# GL3520_4_Ports.net
KiCad netlist of a schematic drawn in Altium Designer
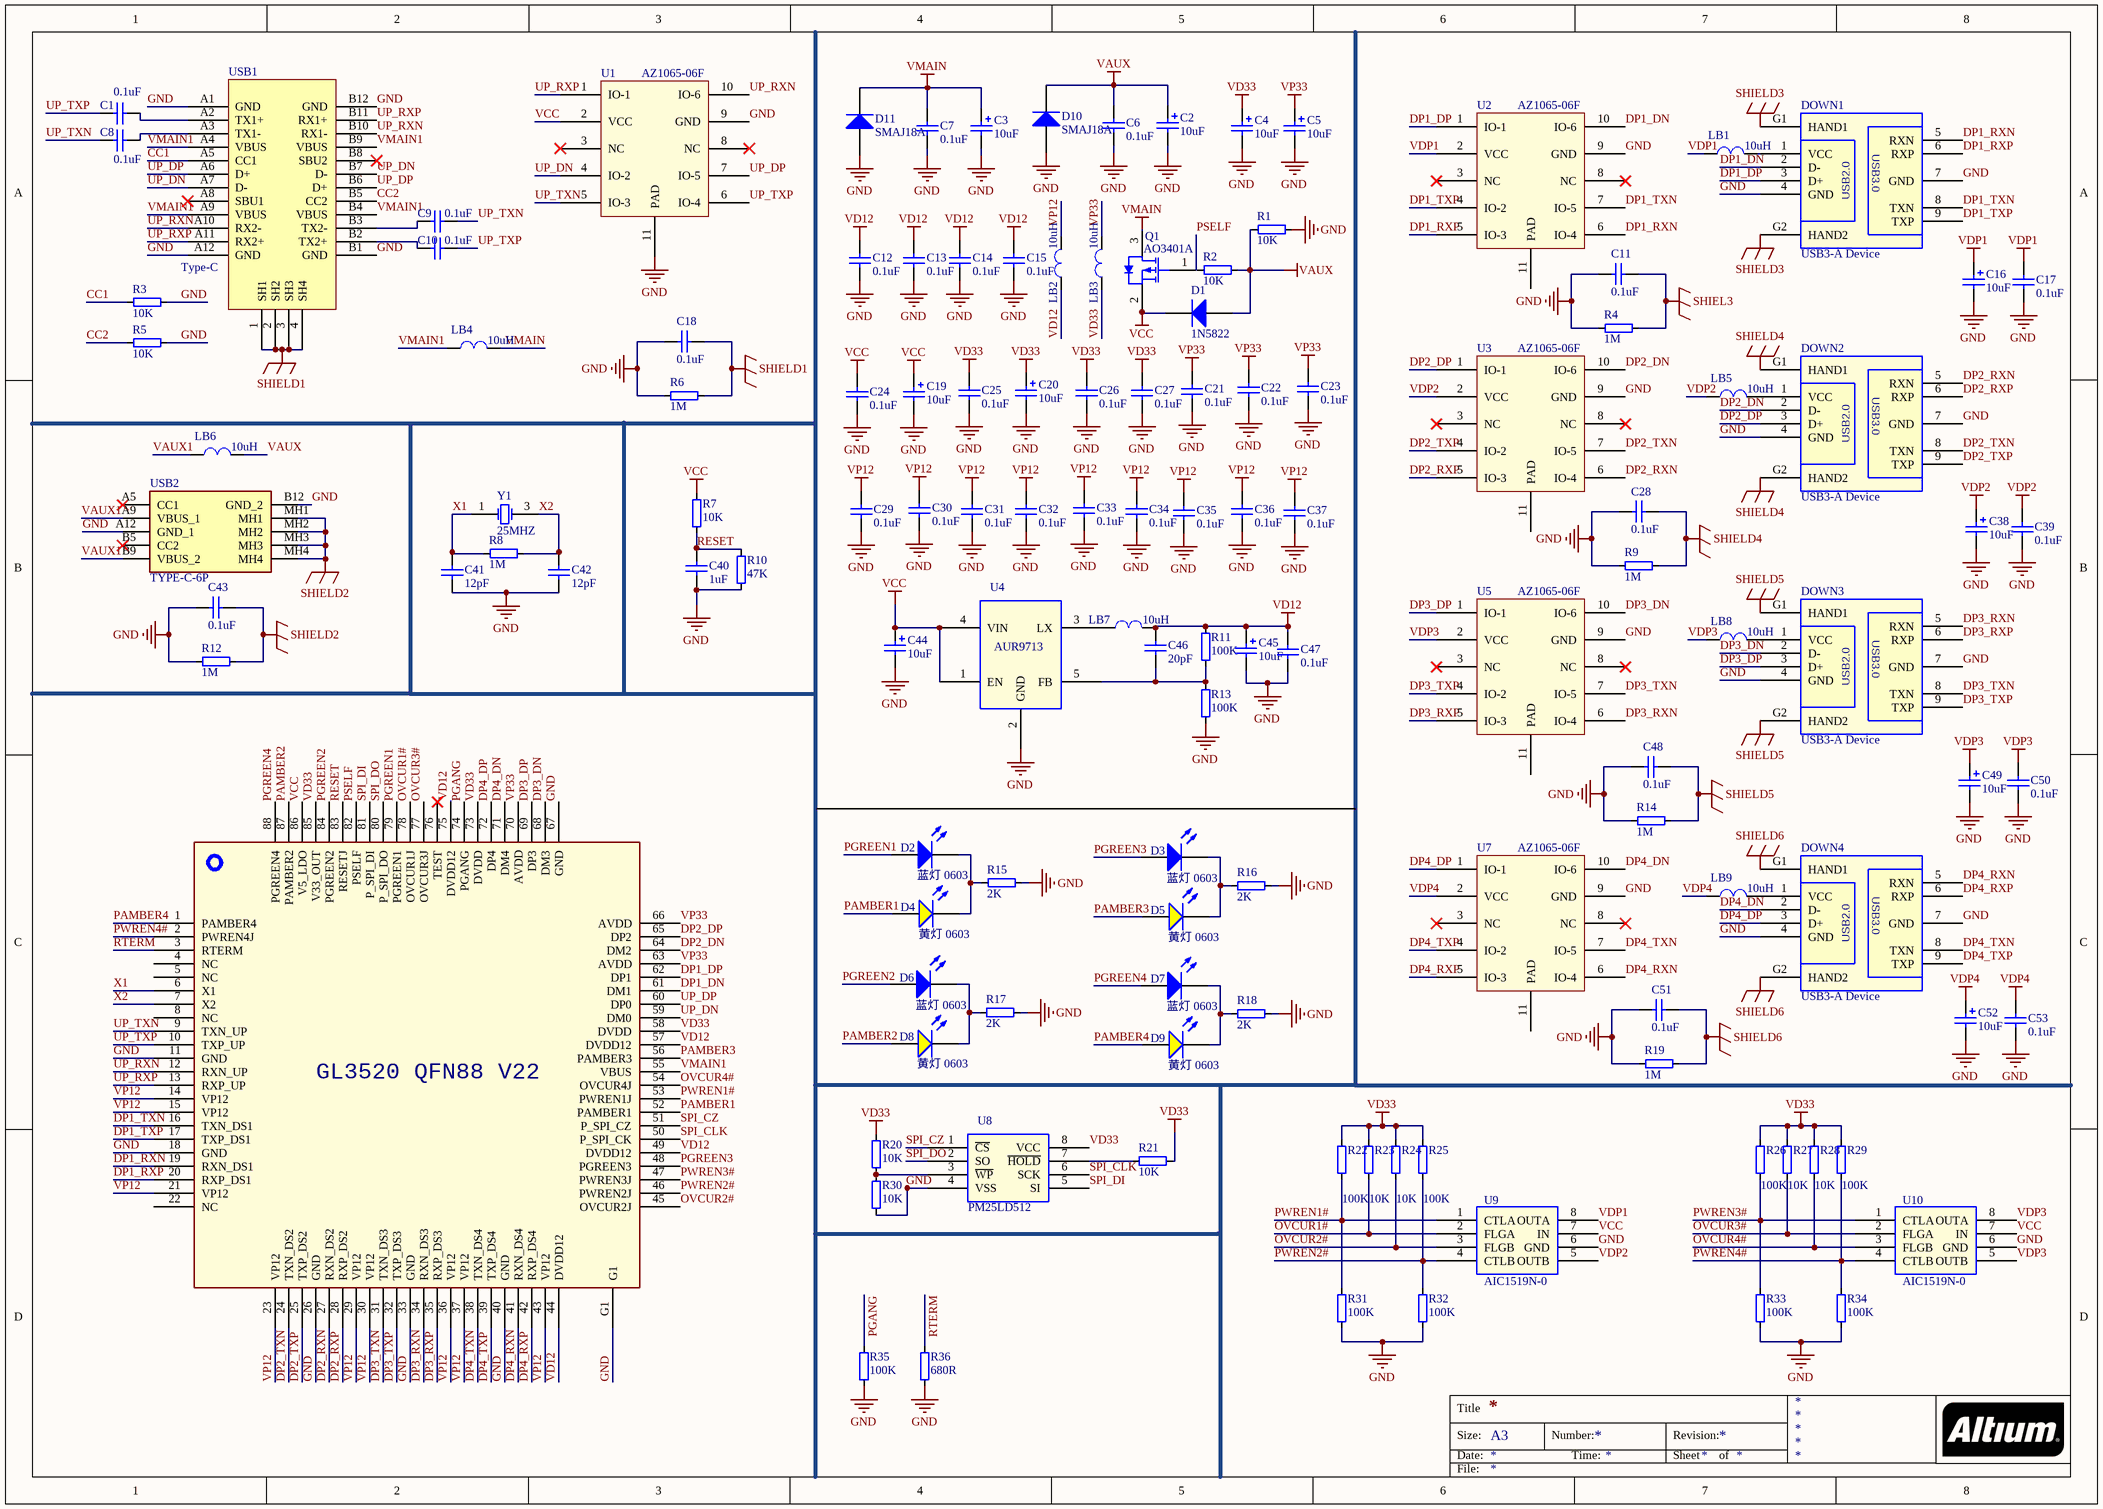
[diagram p0: GL3520 4 Ports.SchDoc]

(export (version "E")
  (design (tool "Eeschema 10.0.6"))
  (components
    (comp (ref "C1")
      (value "0.1uF")
      (footprint "C 0603_L")
      (description "贴片电容")
      (libsource (lib "嘉立创") (part "0603 2.2uF (225) 10% 16V"))
    )
    (comp (ref "C2")
      (value "10uF")
      (footprint "CASE-A_3216")
      (description "钽电容1206")
      (libsource (lib "嘉立创") (part "3216 10uF (106) 10% 16V"))
    )
    (comp (ref "C3")
      (value "10uF")
      (footprint "CASE-A_3216")
      (description "钽电容1206")
      (libsource (lib "嘉立创") (part "3216 10uF (106) 10% 16V"))
    )
    (comp (ref "C4")
      (value "10uF")
      (footprint "CASE-A_3216")
      (description "钽电容")
      (libsource (lib "嘉立创") (part "3216 10uF (106) 10% 16V"))
    )
    (comp (ref "C5")
      (value "10uF")
      (footprint "CASE-A_3216")
      (description "钽电容")
      (libsource (lib "嘉立创") (part "3216 10uF (106) 10% 16V"))
    )
    (comp (ref "C6")
      (value "0.1uF")
      (footprint "C 0603_L")
      (description "贴片电容")
      (libsource (lib "嘉立创") (part "0603 2.2uF (225) 10% 16V"))
    )
    (comp (ref "C7")
      (value "0.1uF")
      (footprint "C 0603_L")
      (description "贴片电容")
      (libsource (lib "嘉立创") (part "0603 2.2uF (225) 10% 16V"))
    )
    (comp (ref "C8")
      (value "0.1uF")
      (footprint "C 0603_L")
      (description "贴片电容")
      (libsource (lib "嘉立创") (part "0603 2.2uF (225) 10% 16V"))
    )
    (comp (ref "C9")
      (value "0.1uF")
      (footprint "C 0603_L")
      (description "贴片电容")
      (libsource (lib "嘉立创") (part "0603 2.2uF (225) 10% 16V"))
    )
    (comp (ref "C10")
      (value "0.1uF")
      (footprint "C 0603_L")
      (description "贴片电容")
      (libsource (lib "嘉立创") (part "0603 2.2uF (225) 10% 16V"))
    )
    (comp (ref "C11")
      (value "0.1uF")
      (footprint "C 0603_L")
      (description "贴片电容")
      (libsource (lib "嘉立创") (part "0603 2.2uF (225) 10% 16V"))
    )
    (comp (ref "C12")
      (value "0.1uF")
      (footprint "C 0603_L")
      (description "贴片电容")
      (libsource (lib "嘉立创") (part "0603 2.2uF (225) 10% 16V"))
    )
    (comp (ref "C13")
      (value "0.1uF")
      (footprint "C 0603_L")
      (description "贴片电容")
      (libsource (lib "嘉立创") (part "0603 2.2uF (225) 10% 16V"))
    )
    (comp (ref "C14")
      (value "0.1uF")
      (footprint "C 0603_L")
      (description "贴片电容")
      (libsource (lib "嘉立创") (part "0603 2.2uF (225) 10% 16V"))
    )
    (comp (ref "C15")
      (value "0.1uF")
      (footprint "C 0603_L")
      (description "贴片电容")
      (libsource (lib "嘉立创") (part "0603 2.2uF (225) 10% 16V"))
    )
    (comp (ref "C16")
      (value "10uF")
      (footprint "CASE-A_3216")
      (description "钽电容")
      (libsource (lib "嘉立创") (part "3216 10uF (106) 10% 16V"))
    )
    (comp (ref "C17")
      (value "0.1uF")
      (footprint "C 0603_L")
      (description "贴片电容")
      (libsource (lib "嘉立创") (part "0603 2.2uF (225) 10% 16V"))
    )
    (comp (ref "C18")
      (value "0.1uF")
      (footprint "C 0603_L")
      (description "贴片电容")
      (libsource (lib "嘉立创") (part "0603 2.2uF (225) 10% 16V"))
    )
    (comp (ref "C19")
      (value "10uF")
      (footprint "CASE-A_3216")
      (description "钽电容1206")
      (libsource (lib "嘉立创") (part "3216 10uF (106) 10% 16V"))
    )
    (comp (ref "C20")
      (value "10uF")
      (footprint "CASE-A_3216")
      (description "钽电容1206")
      (libsource (lib "嘉立创") (part "3216 10uF (106) 10% 16V"))
    )
    (comp (ref "C21")
      (value "0.1uF")
      (footprint "C 0603_L")
      (description "贴片电容")
      (libsource (lib "嘉立创") (part "0603 2.2uF (225) 10% 16V"))
    )
    (comp (ref "C22")
      (value "0.1uF")
      (footprint "C 0603_L")
      (description "贴片电容")
      (libsource (lib "嘉立创") (part "0603 2.2uF (225) 10% 16V"))
    )
    (comp (ref "C23")
      (value "0.1uF")
      (footprint "C 0603_L")
      (description "贴片电容")
      (libsource (lib "嘉立创") (part "0603 2.2uF (225) 10% 16V"))
    )
    (comp (ref "C24")
      (value "0.1uF")
      (footprint "C 0603_L")
      (description "贴片电容")
      (libsource (lib "嘉立创") (part "0603 2.2uF (225) 10% 16V"))
    )
    (comp (ref "C25")
      (value "0.1uF")
      (footprint "C 0603_L")
      (description "贴片电容")
      (libsource (lib "嘉立创") (part "0603 2.2uF (225) 10% 16V"))
    )
    (comp (ref "C26")
      (value "0.1uF")
      (footprint "C 0603_L")
      (description "贴片电容")
      (libsource (lib "嘉立创") (part "0603 2.2uF (225) 10% 16V"))
    )
    (comp (ref "C27")
      (value "0.1uF")
      (footprint "C 0603_L")
      (description "贴片电容")
      (libsource (lib "嘉立创") (part "0603 2.2uF (225) 10% 16V"))
    )
    (comp (ref "C28")
      (value "0.1uF")
      (footprint "C 0603_L")
      (description "贴片电容")
      (libsource (lib "嘉立创") (part "0603 2.2uF (225) 10% 16V"))
    )
    (comp (ref "C29")
      (value "0.1uF")
      (footprint "C 0603_L")
      (description "贴片电容")
      (libsource (lib "嘉立创") (part "0603 2.2uF (225) 10% 16V"))
    )
    (comp (ref "C30")
      (value "0.1uF")
      (footprint "C 0603_L")
      (description "贴片电容")
      (libsource (lib "嘉立创") (part "0603 2.2uF (225) 10% 16V"))
    )
    (comp (ref "C31")
      (value "0.1uF")
      (footprint "C 0603_L")
      (description "贴片电容")
      (libsource (lib "嘉立创") (part "0603 2.2uF (225) 10% 16V"))
    )
    (comp (ref "C32")
      (value "0.1uF")
      (footprint "C 0603_L")
      (description "贴片电容")
      (libsource (lib "嘉立创") (part "0603 2.2uF (225) 10% 16V"))
    )
    (comp (ref "C33")
      (value "0.1uF")
      (footprint "C 0603_L")
      (description "贴片电容")
      (libsource (lib "嘉立创") (part "0603 2.2uF (225) 10% 16V"))
    )
    (comp (ref "C34")
      (value "0.1uF")
      (footprint "C 0603_L")
      (description "贴片电容")
      (libsource (lib "嘉立创") (part "0603 2.2uF (225) 10% 16V"))
    )
    (comp (ref "C35")
      (value "0.1uF")
      (footprint "C 0603_L")
      (description "贴片电容")
      (libsource (lib "嘉立创") (part "0603 2.2uF (225) 10% 16V"))
    )
    (comp (ref "C36")
      (value "0.1uF")
      (footprint "C 0603_L")
      (description "贴片电容")
      (libsource (lib "嘉立创") (part "0603 2.2uF (225) 10% 16V"))
    )
    (comp (ref "C37")
      (value "0.1uF")
      (footprint "C 0603_L")
      (description "贴片电容")
      (libsource (lib "嘉立创") (part "0603 2.2uF (225) 10% 16V"))
    )
    (comp (ref "C38")
      (value "10uF")
      (footprint "CASE-A_3216")
      (description "钽电容")
      (libsource (lib "嘉立创") (part "3216 10uF (106) 10% 16V"))
    )
    (comp (ref "C39")
      (value "0.1uF")
      (footprint "C 0603_L")
      (description "贴片电容")
      (libsource (lib "嘉立创") (part "0603 2.2uF (225) 10% 16V"))
    )
    (comp (ref "C40")
      (value "1uF")
      (footprint "C 0603_L")
      (description "贴片电容")
      (libsource (lib "嘉立创") (part "0603 2.2uF (225) 10% 16V"))
    )
    (comp (ref "C41")
      (value "12pF")
      (footprint "C 0603_L")
      (description "贴片电容")
      (libsource (lib "嘉立创") (part "0603 2.2uF (225) 10% 16V"))
    )
    (comp (ref "C42")
      (value "12pF")
      (footprint "C 0603_L")
      (description "贴片电容")
      (libsource (lib "嘉立创") (part "0603 2.2uF (225) 10% 16V"))
    )
    (comp (ref "C43")
      (value "0.1uF")
      (footprint "C 0603_L")
      (description "贴片电容")
      (libsource (lib "嘉立创") (part "0603 2.2uF (225) 10% 16V"))
    )
    (comp (ref "C44")
      (value "10uF")
      (footprint "CASE-A_3216")
      (description "钽电容")
      (libsource (lib "嘉立创") (part "3216 10uF (106) 10% 16V"))
    )
    (comp (ref "C45")
      (value "10uF")
      (footprint "CASE-A_3216")
      (description "钽电容")
      (libsource (lib "嘉立创") (part "3216 10uF (106) 10% 16V"))
    )
    (comp (ref "C46")
      (value "20pF")
      (footprint "C 0603_L")
      (description "贴片电容")
      (libsource (lib "嘉立创") (part "0603 2.2uF (225) 10% 16V"))
    )
    (comp (ref "C47")
      (value "0.1uF")
      (footprint "C 0603_L")
      (description "贴片电容")
      (libsource (lib "嘉立创") (part "0603 2.2uF (225) 10% 16V"))
    )
    (comp (ref "C48")
      (value "0.1uF")
      (footprint "C 0603_L")
      (description "贴片电容")
      (libsource (lib "嘉立创") (part "0603 2.2uF (225) 10% 16V"))
    )
    (comp (ref "C49")
      (value "10uF")
      (footprint "CASE-A_3216")
      (description "钽电容")
      (libsource (lib "嘉立创") (part "3216 10uF (106) 10% 16V"))
    )
    (comp (ref "C50")
      (value "0.1uF")
      (footprint "C 0603_L")
      (description "贴片电容")
      (libsource (lib "嘉立创") (part "0603 2.2uF (225) 10% 16V"))
    )
    (comp (ref "C51")
      (value "0.1uF")
      (footprint "C 0603_L")
      (description "贴片电容")
      (libsource (lib "嘉立创") (part "0603 2.2uF (225) 10% 16V"))
    )
    (comp (ref "C52")
      (value "10uF")
      (footprint "CASE-A_3216")
      (description "钽电容")
      (libsource (lib "嘉立创") (part "3216 10uF (106) 10% 16V"))
    )
    (comp (ref "C53")
      (value "0.1uF")
      (footprint "C 0603_L")
      (description "贴片电容")
      (libsource (lib "嘉立创") (part "0603 2.2uF (225) 10% 16V"))
    )
    (comp (ref "D1")
      (value "1N5822")
      (footprint "SMA")
      (description "3 Amp General Purpose Rectifier")
      (fields (field (name "PUBLISHER") "Altium Limited"))
      (libsource (lib "Miscellaneous Devices") (part "Diode 1N5400"))
    )
    (comp (ref "D2")
      (value "蓝灯 0603")
      (footprint "0603_LED_S1")
      (description "发光二极管")
      (libsource (lib "嘉立创") (part "0603 蓝灯"))
    )
    (comp (ref "D3")
      (value "蓝灯 0603")
      (footprint "0603_LED_S1")
      (description "发光二极管")
      (libsource (lib "嘉立创") (part "0603 蓝灯"))
    )
    (comp (ref "D4")
      (value "黄灯 0603")
      (footprint "0603_LED_S1")
      (description "发光二极管")
      (libsource (lib "嘉立创") (part "0603 黄灯"))
    )
    (comp (ref "D5")
      (value "黄灯 0603")
      (footprint "0603_LED_S1")
      (description "发光二极管")
      (libsource (lib "嘉立创") (part "0603 黄灯"))
    )
    (comp (ref "D6")
      (value "蓝灯 0603")
      (footprint "0603_LED_S1")
      (description "发光二极管")
      (libsource (lib "嘉立创") (part "0603 蓝灯"))
    )
    (comp (ref "D7")
      (value "蓝灯 0603")
      (footprint "0603_LED_S1")
      (description "发光二极管")
      (libsource (lib "嘉立创") (part "0603 蓝灯"))
    )
    (comp (ref "D8")
      (value "黄灯 0603")
      (footprint "0603_LED_S1")
      (description "发光二极管")
      (libsource (lib "嘉立创") (part "0603 黄灯"))
    )
    (comp (ref "D9")
      (value "黄灯 0603")
      (footprint "0603_LED_S1")
      (description "发光二极管")
      (libsource (lib "嘉立创") (part "0603 黄灯"))
    )
    (comp (ref "D10")
      (value "SMAJ18A")
      (footprint "DIO-214AC")
      (description "3 Amp General Purpose Rectifier")
      (fields (field (name "PUBLISHER") "Altium Limited"))
      (libsource (lib "Miscellaneous Devices") (part "Diode 1N5400"))
    )
    (comp (ref "D11")
      (value "SMAJ18A")
      (footprint "DIO-214AC")
      (description "3 Amp General Purpose Rectifier")
      (fields (field (name "PUBLISHER") "Altium Limited"))
      (libsource (lib "Miscellaneous Devices") (part "Diode 1N5400"))
    )
    (comp (ref "DOWN1")
      (value "USB3-A Device")
      (footprint "USB3.0-2 - duplicate")
      (libsource (lib "*") (part "USB3-A_5"))
    )
    (comp (ref "DOWN2")
      (value "USB3-A Device")
      (footprint "USB3.0-2 - duplicate")
      (libsource (lib "*") (part "USB3-A_5"))
    )
    (comp (ref "DOWN3")
      (value "USB3-A Device")
      (footprint "USB3.0-2 - duplicate")
      (libsource (lib "*") (part "USB3-A_5"))
    )
    (comp (ref "DOWN4")
      (value "USB3-A Device")
      (footprint "USB3.0-2 - duplicate")
      (libsource (lib "*") (part "USB3-A_5"))
    )
    (comp (ref "LB1") (value "10uH") (footprint "CDRH74") (libsource (lib "*") (part "L-0603")))
    (comp (ref "LB2") (value "10uH") (footprint "CDRH74") (libsource (lib "*") (part "L-0603")))
    (comp (ref "LB3") (value "10uH") (footprint "CDRH74") (libsource (lib "*") (part "L-0603")))
    (comp (ref "LB4") (value "10uH") (footprint "CDRH74") (libsource (lib "*") (part "L-0603")))
    (comp (ref "LB5") (value "10uH") (footprint "CDRH74") (libsource (lib "*") (part "L-0603")))
    (comp (ref "LB6") (value "10uH") (footprint "CDRH74") (libsource (lib "*") (part "L-0603")))
    (comp (ref "LB7") (value "10uH") (footprint "CDRH74") (libsource (lib "*") (part "L-0603")))
    (comp (ref "LB8") (value "10uH") (footprint "CDRH74") (libsource (lib "*") (part "L-0603")))
    (comp (ref "LB9") (value "10uH") (footprint "CDRH74") (libsource (lib "*") (part "L-0603")))
    (comp (ref "Q1")
      (value "AO3401A")
      (footprint "SOT23-3L")
      (description "P-Channel MOSFET, 30 V, 4 A, -55 to 150 degC, 3-Pin SOT-23-3L, RoHS, Tape and Reel")
      (fields (field (name "MANUFACTURER") "Alpha and Omega"))
      (libsource (lib "GL3520 4 Ports") (part "CMP-2000-05778-1"))
    )
    (comp (ref "R1") (value "10K") (footprint "R 0603_L") (libsource (lib "Jlink OB") (part "RES")))
    (comp (ref "R2") (value "10K") (footprint "R 0603_L") (libsource (lib "Jlink OB") (part "RES")))
    (comp (ref "R3") (value "10K") (footprint "R 0603_L") (libsource (lib "Jlink OB") (part "RES")))
    (comp (ref "R4") (value "1M") (footprint "R 0603_L") (libsource (lib "Jlink OB") (part "RES")))
    (comp (ref "R5") (value "10K") (footprint "R 0603_L") (libsource (lib "Jlink OB") (part "RES")))
    (comp (ref "R6") (value "1M") (footprint "R 0603_L") (libsource (lib "Jlink OB") (part "RES")))
    (comp (ref "R7") (value "10K") (footprint "R 0603_L") (libsource (lib "Jlink OB") (part "RES")))
    (comp (ref "R8") (value "1M") (footprint "R 0603_L") (libsource (lib "Jlink OB") (part "RES")))
    (comp (ref "R9") (value "1M") (footprint "R 0603_L") (libsource (lib "Jlink OB") (part "RES")))
    (comp (ref "R10") (value "47K") (footprint "R 0603_L") (libsource (lib "Jlink OB") (part "RES")))
    (comp (ref "R11") (value "100K") (footprint "R 0603_L") (libsource (lib "Jlink OB") (part "RES")))
    (comp (ref "R12") (value "1M") (footprint "R 0603_L") (libsource (lib "Jlink OB") (part "RES")))
    (comp (ref "R13") (value "100K") (footprint "R 0603_L") (libsource (lib "Jlink OB") (part "RES")))
    (comp (ref "R14") (value "1M") (footprint "R 0603_L") (libsource (lib "Jlink OB") (part "RES")))
    (comp (ref "R15") (value "2K") (footprint "R 0603_L") (libsource (lib "Jlink OB") (part "RES")))
    (comp (ref "R16") (value "2K") (footprint "R 0603_L") (libsource (lib "Jlink OB") (part "RES")))
    (comp (ref "R17") (value "2K") (footprint "R 0603_L") (libsource (lib "Jlink OB") (part "RES")))
    (comp (ref "R18") (value "2K") (footprint "R 0603_L") (libsource (lib "Jlink OB") (part "RES")))
    (comp (ref "R19") (value "1M") (footprint "R 0603_L") (libsource (lib "Jlink OB") (part "RES")))
    (comp (ref "R20") (value "10K") (footprint "R 0603_L") (libsource (lib "Jlink OB") (part "RES")))
    (comp (ref "R21") (value "10K") (footprint "R 0603_L") (libsource (lib "Jlink OB") (part "RES")))
    (comp (ref "R22") (value "100K") (footprint "R 0603_L") (libsource (lib "Jlink OB") (part "RES")))
    (comp (ref "R23") (value "10K") (footprint "R 0603_L") (libsource (lib "Jlink OB") (part "RES")))
    (comp (ref "R24") (value "10K") (footprint "R 0603_L") (libsource (lib "Jlink OB") (part "RES")))
    (comp (ref "R25") (value "100K") (footprint "R 0603_L") (libsource (lib "Jlink OB") (part "RES")))
    (comp (ref "R26") (value "100K") (footprint "R 0603_L") (libsource (lib "Jlink OB") (part "RES")))
    (comp (ref "R27") (value "10K") (footprint "R 0603_L") (libsource (lib "Jlink OB") (part "RES")))
    (comp (ref "R28") (value "10K") (footprint "R 0603_L") (libsource (lib "Jlink OB") (part "RES")))
    (comp (ref "R29") (value "100K") (footprint "R 0603_L") (libsource (lib "Jlink OB") (part "RES")))
    (comp (ref "R30") (value "10K") (footprint "R 0603_L") (libsource (lib "Jlink OB") (part "RES")))
    (comp (ref "R31") (value "100K") (footprint "R 0603_L") (libsource (lib "Jlink OB") (part "RES")))
    (comp (ref "R32") (value "100K") (footprint "R 0603_L") (libsource (lib "Jlink OB") (part "RES")))
    (comp (ref "R33") (value "100K") (footprint "R 0603_L") (libsource (lib "Jlink OB") (part "RES")))
    (comp (ref "R34") (value "100K") (footprint "R 0603_L") (libsource (lib "Jlink OB") (part "RES")))
    (comp (ref "R35") (value "100K") (footprint "R 0603_L") (libsource (lib "Jlink OB") (part "RES")))
    (comp (ref "R36") (value "680R") (footprint "R 0603_L") (libsource (lib "Jlink OB") (part "RES")))
    (comp (ref "U1")
      (value "AZ1065-06F")
      (footprint "DFN4120P10E")
      (description "晶炎AZ1065-06F.R7G DFN4120 丝印119 ESD/TVS静电保护二极管")
      (libsource (lib "GL3520 4 Ports") (part "AZ1065-06F"))
    )
    (comp (ref "U2")
      (value "AZ1065-06F")
      (footprint "DFN4120P10E")
      (description "晶炎AZ1065-06F.R7G DFN4120 丝印119 ESD/TVS静电保护二极管")
      (libsource (lib "GL3520 4 Ports") (part "AZ1065-06F"))
    )
    (comp (ref "U3")
      (value "AZ1065-06F")
      (footprint "DFN4120P10E")
      (description "晶炎AZ1065-06F.R7G DFN4120 丝印119 ESD/TVS静电保护二极管")
      (libsource (lib "GL3520 4 Ports") (part "AZ1065-06F"))
    )
    (comp (ref "U4") (value "AUR9713") (footprint "SOT23-5L") (libsource (lib "*") (part "AUR9705_3")))
    (comp (ref "U5")
      (value "AZ1065-06F")
      (footprint "DFN4120P10E")
      (description "晶炎AZ1065-06F.R7G DFN4120 丝印119 ESD/TVS静电保护二极管")
      (libsource (lib "GL3520 4 Ports") (part "AZ1065-06F"))
    )
    (comp (ref "U6")
      (value "GL3520_QFN88_V094-1_22")
      (footprint "QFN88")
      (libsource (lib "GL3520 4 Ports") (part "GL3520_QFN88_V094-1_22"))
    )
    (comp (ref "U7")
      (value "AZ1065-06F")
      (footprint "DFN4120P10E")
      (description "晶炎AZ1065-06F.R7G DFN4120 丝印119 ESD/TVS静电保护二极管")
      (libsource (lib "GL3520 4 Ports") (part "AZ1065-06F"))
    )
    (comp (ref "U8") (value "PM25LD512") (footprint "SOP8W_M") (libsource (lib "*") (part "CAT25C128/256")))
    (comp (ref "U9") (value "AIC1519N-0") (footprint "SOP8_L") (libsource (lib "*") (part "AIC1526-SOP")))
    (comp (ref "U10") (value "AIC1519N-0") (footprint "SOP8_L") (libsource (lib "*") (part "AIC1526-SOP")))
    (comp (ref "USB1")
      (value "Type-C")
      (footprint "USB_TYPE_C_24P - duplicate")
      (libsource (lib "Jlink OB") (part "Type-C"))
    )
    (comp (ref "USB2")
      (value "TYPE-C-6P")
      (footprint "USB_TYPE_C_6P")
      (description "Connector")
      (fields (field (name "MANUFACTURER_PART_NUMBER") "TYPE-C-31-M-17"))
      (libsource (lib "SamacSys") (part "TYPE-C-31-M-17"))
    )
    (comp (ref "Y1")
      (value "25MHZ")
      (footprint "OSC 3225-4P")
      (description "贴片晶振")
      (libsource (lib "嘉立创") (part "SMD-3225_4P  25MHZ 12PF 10PPM"))
    )
  )
  (nets
    (net (code "1") (name "/CC1") (class "Default")
      (node (ref "R3") (pin "1") (pinfunction "1_1") (pintype "passive"))
      (node (ref "USB1") (pin "A5") (pinfunction "CC1_A5") (pintype "passive"))
    )
    (net (code "2") (name "/CC2") (class "Default")
      (node (ref "R5") (pin "1") (pinfunction "1_1") (pintype "passive"))
      (node (ref "USB1") (pin "B5") (pinfunction "CC2_B5") (pintype "passive"))
    )
    (net (code "3") (name "/DP1_DN") (class "Default")
      (node (ref "DOWN1") (pin "2") (pinfunction "D-_2") (pintype "passive"))
      (node (ref "U2") (pin "10") (pinfunction "IO-6_10") (pintype "passive"))
      (node (ref "U6") (pin "61") (pinfunction "DM1_61") (pintype "passive"))
    )
    (net (code "4") (name "/DP1_DP") (class "Default")
      (node (ref "DOWN1") (pin "3") (pinfunction "D+_3") (pintype "passive"))
      (node (ref "U2") (pin "1") (pinfunction "IO-1_1") (pintype "passive"))
      (node (ref "U6") (pin "62") (pinfunction "DP1_62") (pintype "passive"))
    )
    (net (code "5") (name "/DP1_RXN") (class "Default")
      (node (ref "DOWN1") (pin "5") (pinfunction "RXN_5") (pintype "passive"))
      (node (ref "U2") (pin "6") (pinfunction "IO-4_6") (pintype "passive"))
      (node (ref "U6") (pin "19") (pinfunction "RXN_DS1_19") (pintype "passive"))
    )
    (net (code "6") (name "/DP1_RXP") (class "Default")
      (node (ref "DOWN1") (pin "6") (pinfunction "RXP_6") (pintype "passive"))
      (node (ref "U2") (pin "5") (pinfunction "IO-3_5") (pintype "passive"))
      (node (ref "U6") (pin "20") (pinfunction "RXP_DS1_20") (pintype "passive"))
    )
    (net (code "7") (name "/DP1_TXN") (class "Default")
      (node (ref "DOWN1") (pin "8") (pinfunction "TXN_8") (pintype "passive"))
      (node (ref "U2") (pin "7") (pinfunction "IO-5_7") (pintype "passive"))
      (node (ref "U6") (pin "16") (pinfunction "TXN_DS1_16") (pintype "passive"))
    )
    (net (code "8") (name "/DP1_TXP") (class "Default")
      (node (ref "DOWN1") (pin "9") (pinfunction "TXP_9") (pintype "passive"))
      (node (ref "U2") (pin "4") (pinfunction "IO-2_4") (pintype "passive"))
      (node (ref "U6") (pin "17") (pinfunction "TXP_DS1_17") (pintype "passive"))
    )
    (net (code "9") (name "/DP2_DN") (class "Default")
      (node (ref "DOWN2") (pin "2") (pinfunction "D-_2") (pintype "passive"))
      (node (ref "U3") (pin "10") (pinfunction "IO-6_10") (pintype "passive"))
      (node (ref "U6") (pin "64") (pinfunction "DM2_64") (pintype "passive"))
    )
    (net (code "10") (name "/DP2_DP") (class "Default")
      (node (ref "DOWN2") (pin "3") (pinfunction "D+_3") (pintype "passive"))
      (node (ref "U3") (pin "1") (pinfunction "IO-1_1") (pintype "passive"))
      (node (ref "U6") (pin "65") (pinfunction "DP2_65") (pintype "passive"))
    )
    (net (code "11") (name "/DP2_RXN") (class "Default")
      (node (ref "DOWN2") (pin "5") (pinfunction "RXN_5") (pintype "passive"))
      (node (ref "U3") (pin "6") (pinfunction "IO-4_6") (pintype "passive"))
      (node (ref "U6") (pin "27") (pinfunction "RXN_DS2_27") (pintype "passive"))
    )
    (net (code "12") (name "/DP2_RXP") (class "Default")
      (node (ref "DOWN2") (pin "6") (pinfunction "RXP_6") (pintype "passive"))
      (node (ref "U3") (pin "5") (pinfunction "IO-3_5") (pintype "passive"))
      (node (ref "U6") (pin "28") (pinfunction "RXP_DS2_28") (pintype "passive"))
    )
    (net (code "13") (name "/DP2_TXN") (class "Default")
      (node (ref "DOWN2") (pin "8") (pinfunction "TXN_8") (pintype "passive"))
      (node (ref "U3") (pin "7") (pinfunction "IO-5_7") (pintype "passive"))
      (node (ref "U6") (pin "24") (pinfunction "TXN_DS2_24") (pintype "passive"))
    )
    (net (code "14") (name "/DP2_TXP") (class "Default")
      (node (ref "DOWN2") (pin "9") (pinfunction "TXP_9") (pintype "passive"))
      (node (ref "U3") (pin "4") (pinfunction "IO-2_4") (pintype "passive"))
      (node (ref "U6") (pin "25") (pinfunction "TXP_DS2_25") (pintype "passive"))
    )
    (net (code "15") (name "/DP3_DN") (class "Default")
      (node (ref "DOWN3") (pin "2") (pinfunction "D-_2") (pintype "passive"))
      (node (ref "U5") (pin "10") (pinfunction "IO-6_10") (pintype "passive"))
      (node (ref "U6") (pin "68") (pinfunction "DM3_68") (pintype "passive"))
    )
    (net (code "16") (name "/DP3_DP") (class "Default")
      (node (ref "DOWN3") (pin "3") (pinfunction "D+_3") (pintype "passive"))
      (node (ref "U5") (pin "1") (pinfunction "IO-1_1") (pintype "passive"))
      (node (ref "U6") (pin "69") (pinfunction "DP3_69") (pintype "passive"))
    )
    (net (code "17") (name "/DP3_RXN") (class "Default")
      (node (ref "DOWN3") (pin "5") (pinfunction "RXN_5") (pintype "passive"))
      (node (ref "U5") (pin "6") (pinfunction "IO-4_6") (pintype "passive"))
      (node (ref "U6") (pin "34") (pinfunction "RXN_DS3_34") (pintype "passive"))
    )
    (net (code "18") (name "/DP3_RXP") (class "Default")
      (node (ref "DOWN3") (pin "6") (pinfunction "RXP_6") (pintype "passive"))
      (node (ref "U5") (pin "5") (pinfunction "IO-3_5") (pintype "passive"))
      (node (ref "U6") (pin "35") (pinfunction "RXP_DS3_35") (pintype "passive"))
    )
    (net (code "19") (name "/DP3_TXN") (class "Default")
      (node (ref "DOWN3") (pin "8") (pinfunction "TXN_8") (pintype "passive"))
      (node (ref "U5") (pin "7") (pinfunction "IO-5_7") (pintype "passive"))
      (node (ref "U6") (pin "31") (pinfunction "TXN_DS3_31") (pintype "passive"))
    )
    (net (code "20") (name "/DP3_TXP") (class "Default")
      (node (ref "DOWN3") (pin "9") (pinfunction "TXP_9") (pintype "passive"))
      (node (ref "U5") (pin "4") (pinfunction "IO-2_4") (pintype "passive"))
      (node (ref "U6") (pin "32") (pinfunction "TXP_DS3_32") (pintype "passive"))
    )
    (net (code "21") (name "/DP4_DN") (class "Default")
      (node (ref "DOWN4") (pin "2") (pinfunction "D-_2") (pintype "passive"))
      (node (ref "U6") (pin "71") (pinfunction "DM4_71") (pintype "passive"))
      (node (ref "U7") (pin "10") (pinfunction "IO-6_10") (pintype "passive"))
    )
    (net (code "22") (name "/DP4_DP") (class "Default")
      (node (ref "DOWN4") (pin "3") (pinfunction "D+_3") (pintype "passive"))
      (node (ref "U6") (pin "72") (pinfunction "DP4_72") (pintype "passive"))
      (node (ref "U7") (pin "1") (pinfunction "IO-1_1") (pintype "passive"))
    )
    (net (code "23") (name "/DP4_RXN") (class "Default")
      (node (ref "DOWN4") (pin "5") (pinfunction "RXN_5") (pintype "passive"))
      (node (ref "U6") (pin "41") (pinfunction "RXN_DS4_41") (pintype "passive"))
      (node (ref "U7") (pin "6") (pinfunction "IO-4_6") (pintype "passive"))
    )
    (net (code "24") (name "/DP4_RXP") (class "Default")
      (node (ref "DOWN4") (pin "6") (pinfunction "RXP_6") (pintype "passive"))
      (node (ref "U6") (pin "42") (pinfunction "RXP_DS4_42") (pintype "passive"))
      (node (ref "U7") (pin "5") (pinfunction "IO-3_5") (pintype "passive"))
    )
    (net (code "25") (name "/DP4_TXN") (class "Default")
      (node (ref "DOWN4") (pin "8") (pinfunction "TXN_8") (pintype "passive"))
      (node (ref "U6") (pin "38") (pinfunction "TXN_DS4_38") (pintype "passive"))
      (node (ref "U7") (pin "7") (pinfunction "IO-5_7") (pintype "passive"))
    )
    (net (code "26") (name "/DP4_TXP") (class "Default")
      (node (ref "DOWN4") (pin "9") (pinfunction "TXP_9") (pintype "passive"))
      (node (ref "U6") (pin "39") (pinfunction "TXP_DS4_39") (pintype "passive"))
      (node (ref "U7") (pin "4") (pinfunction "IO-2_4") (pintype "passive"))
    )
    (net (code "27") (name "/OVCUR1#") (class "Default")
      (node (ref "R23") (pin "2") (pinfunction "2_2") (pintype "passive"))
      (node (ref "U6") (pin "78") (pinfunction "OVCUR1J_78") (pintype "passive"))
      (node (ref "U9") (pin "2") (pinfunction "FLGA_2") (pintype "passive"))
    )
    (net (code "28") (name "/OVCUR2#") (class "Default")
      (node (ref "R24") (pin "2") (pinfunction "2_2") (pintype "passive"))
      (node (ref "U6") (pin "45") (pinfunction "OVCUR2J_45") (pintype "passive"))
      (node (ref "U9") (pin "3") (pinfunction "FLGB_3") (pintype "passive"))
    )
    (net (code "29") (name "/OVCUR3#") (class "Default")
      (node (ref "R27") (pin "2") (pinfunction "2_2") (pintype "passive"))
      (node (ref "U10") (pin "2") (pinfunction "FLGA_2") (pintype "passive"))
      (node (ref "U6") (pin "77") (pinfunction "OVCUR3J_77") (pintype "passive"))
    )
    (net (code "30") (name "/OVCUR4#") (class "Default")
      (node (ref "R28") (pin "2") (pinfunction "2_2") (pintype "passive"))
      (node (ref "U10") (pin "3") (pinfunction "FLGB_3") (pintype "passive"))
      (node (ref "U6") (pin "54") (pinfunction "OVCUR4J_54") (pintype "passive"))
    )
    (net (code "31") (name "/PAMBER1") (class "Default")
      (node (ref "D4") (pin "A") (pinfunction "A_A") (pintype "passive"))
      (node (ref "U6") (pin "52") (pinfunction "PAMBER1_52") (pintype "passive"))
    )
    (net (code "32") (name "/PAMBER2") (class "Default")
      (node (ref "D8") (pin "A") (pinfunction "A_A") (pintype "passive"))
      (node (ref "U6") (pin "87") (pinfunction "PAMBER2_87") (pintype "passive"))
    )
    (net (code "33") (name "/PAMBER3") (class "Default")
      (node (ref "D5") (pin "A") (pinfunction "A_A") (pintype "passive"))
      (node (ref "U6") (pin "56") (pinfunction "PAMBER3_56") (pintype "passive"))
    )
    (net (code "34") (name "/PAMBER4") (class "Default")
      (node (ref "D9") (pin "A") (pinfunction "A_A") (pintype "passive"))
      (node (ref "U6") (pin "1") (pinfunction "PAMBER4_1") (pintype "passive"))
    )
    (net (code "35") (name "/PGANG") (class "Default")
      (node (ref "R35") (pin "1") (pinfunction "1_1") (pintype "passive"))
      (node (ref "U6") (pin "74") (pinfunction "PGANG_74") (pintype "passive"))
    )
    (net (code "36") (name "/PGREEN1") (class "Default")
      (node (ref "D2") (pin "A") (pinfunction "A_A") (pintype "passive"))
      (node (ref "U6") (pin "79") (pinfunction "PGREEN1_79") (pintype "passive"))
    )
    (net (code "37") (name "/PGREEN2") (class "Default")
      (node (ref "D6") (pin "A") (pinfunction "A_A") (pintype "passive"))
      (node (ref "U6") (pin "84") (pinfunction "PGREEN2_84") (pintype "passive"))
    )
    (net (code "38") (name "/PGREEN3") (class "Default")
      (node (ref "D3") (pin "A") (pinfunction "A_A") (pintype "passive"))
      (node (ref "U6") (pin "48") (pinfunction "PGREEN3_48") (pintype "passive"))
    )
    (net (code "39") (name "/PGREEN4") (class "Default")
      (node (ref "D7") (pin "A") (pinfunction "A_A") (pintype "passive"))
      (node (ref "U6") (pin "88") (pinfunction "PGREEN4_88") (pintype "passive"))
    )
    (net (code "40") (name "/PSELF") (class "Default")
      (node (ref "Q1") (pin "1") (pinfunction "GATE_1") (pintype "passive"))
      (node (ref "U6") (pin "82") (pinfunction "PSELF_82") (pintype "passive"))
    )
    (net (code "41") (name "/PWREN1#") (class "Default")
      (node (ref "R22") (pin "2") (pinfunction "2_2") (pintype "passive"))
      (node (ref "R31") (pin "1") (pinfunction "1_1") (pintype "passive"))
      (node (ref "U6") (pin "53") (pinfunction "PWREN1J_53") (pintype "passive"))
      (node (ref "U9") (pin "1") (pinfunction "CTLA_1") (pintype "passive"))
    )
    (net (code "42") (name "/PWREN2#") (class "Default")
      (node (ref "R25") (pin "2") (pinfunction "2_2") (pintype "passive"))
      (node (ref "R32") (pin "1") (pinfunction "1_1") (pintype "passive"))
      (node (ref "U6") (pin "46") (pinfunction "PWREN2J_46") (pintype "passive"))
      (node (ref "U9") (pin "4") (pinfunction "CTLB_4") (pintype "passive"))
    )
    (net (code "43") (name "/PWREN3#") (class "Default")
      (node (ref "R26") (pin "2") (pinfunction "2_2") (pintype "passive"))
      (node (ref "R33") (pin "1") (pinfunction "1_1") (pintype "passive"))
      (node (ref "U10") (pin "1") (pinfunction "CTLA_1") (pintype "passive"))
      (node (ref "U6") (pin "47") (pinfunction "PWREN3J_47") (pintype "passive"))
    )
    (net (code "44") (name "/PWREN4#") (class "Default")
      (node (ref "R29") (pin "2") (pinfunction "2_2") (pintype "passive"))
      (node (ref "R34") (pin "1") (pinfunction "1_1") (pintype "passive"))
      (node (ref "U10") (pin "4") (pinfunction "CTLB_4") (pintype "passive"))
      (node (ref "U6") (pin "2") (pinfunction "PWREN4J_2") (pintype "passive"))
    )
    (net (code "45") (name "/RESET") (class "Default")
      (node (ref "C40") (pin "2") (pinfunction "2_2") (pintype "passive"))
      (node (ref "R10") (pin "2") (pinfunction "2_2") (pintype "passive"))
      (node (ref "R7") (pin "1") (pinfunction "1_1") (pintype "passive"))
      (node (ref "U6") (pin "83") (pinfunction "RESETJ_83") (pintype "passive"))
    )
    (net (code "46") (name "/RTERM") (class "Default")
      (node (ref "R36") (pin "1") (pinfunction "1_1") (pintype "passive"))
      (node (ref "U6") (pin "3") (pinfunction "RTERM_3") (pintype "passive"))
    )
    (net (code "47") (name "/SPI_CLK") (class "Default")
      (node (ref "U6") (pin "50") (pinfunction "P_SPI_CK_50") (pintype "passive"))
      (node (ref "U8") (pin "6") (pinfunction "SCK_6") (pintype "passive"))
    )
    (net (code "48") (name "/SPI_CZ") (class "Default")
      (node (ref "U6") (pin "51") (pinfunction "P_SPI_CZ_51") (pintype "passive"))
      (node (ref "U8") (pin "1") (pinfunction "~{CS}_1") (pintype "passive"))
    )
    (net (code "49") (name "/SPI_DI") (class "Default")
      (node (ref "U6") (pin "81") (pinfunction "P_SPI_DI_81") (pintype "passive"))
      (node (ref "U8") (pin "5") (pinfunction "SI_5") (pintype "passive"))
    )
    (net (code "50") (name "/SPI_DO") (class "Default")
      (node (ref "U6") (pin "80") (pinfunction "P_SPI_DO_80") (pintype "passive"))
      (node (ref "U8") (pin "2") (pinfunction "SO_2") (pintype "passive"))
    )
    (net (code "51") (name "/UP_DN") (class "Default")
      (node (ref "U1") (pin "4") (pinfunction "IO-2_4") (pintype "passive"))
      (node (ref "U6") (pin "59") (pinfunction "DM0_59") (pintype "passive"))
      (node (ref "USB1") (pin "A7") (pinfunction "D-_A7") (pintype "passive"))
      (node (ref "USB1") (pin "B7") (pinfunction "D-_B7") (pintype "passive"))
    )
    (net (code "52") (name "/UP_DP") (class "Default")
      (node (ref "U1") (pin "7") (pinfunction "IO-5_7") (pintype "passive"))
      (node (ref "U6") (pin "60") (pinfunction "DP0_60") (pintype "passive"))
      (node (ref "USB1") (pin "A6") (pinfunction "D+_A6") (pintype "passive"))
      (node (ref "USB1") (pin "B6") (pinfunction "D+_B6") (pintype "passive"))
    )
    (net (code "53") (name "/UP_RXN") (class "Default")
      (node (ref "U1") (pin "10") (pinfunction "IO-6_10") (pintype "passive"))
      (node (ref "U6") (pin "12") (pinfunction "RXN_UP_12") (pintype "passive"))
      (node (ref "USB1") (pin "A10") (pinfunction "RX2-_A10") (pintype "passive"))
      (node (ref "USB1") (pin "B10") (pinfunction "RX1-_B10") (pintype "passive"))
    )
    (net (code "54") (name "/UP_RXP") (class "Default")
      (node (ref "U1") (pin "1") (pinfunction "IO-1_1") (pintype "passive"))
      (node (ref "U6") (pin "13") (pinfunction "RXP_UP_13") (pintype "passive"))
      (node (ref "USB1") (pin "A11") (pinfunction "RX2+_A11") (pintype "passive"))
      (node (ref "USB1") (pin "B11") (pinfunction "RX1+_B11") (pintype "passive"))
    )
    (net (code "55") (name "/UP_TXN") (class "Default")
      (node (ref "C8") (pin "2") (pinfunction "2_2") (pintype "passive"))
      (node (ref "C9") (pin "1") (pinfunction "1_1") (pintype "passive"))
      (node (ref "U1") (pin "5") (pinfunction "IO-3_5") (pintype "passive"))
      (node (ref "U6") (pin "9") (pinfunction "TXN_UP_9") (pintype "passive"))
    )
    (net (code "56") (name "/UP_TXP") (class "Default")
      (node (ref "C1") (pin "2") (pinfunction "2_2") (pintype "passive"))
      (node (ref "C10") (pin "1") (pinfunction "1_1") (pintype "passive"))
      (node (ref "U1") (pin "6") (pinfunction "IO-4_6") (pintype "passive"))
      (node (ref "U6") (pin "10") (pinfunction "TXP_UP_10") (pintype "passive"))
    )
    (net (code "57") (name "/VAUX1") (class "Default")
      (node (ref "LB6") (pin "1") (pinfunction "1_1") (pintype "passive"))
      (node (ref "USB2") (pin "A9") (pinfunction "VBUS_1_A9") (pintype "passive"))
      (node (ref "USB2") (pin "B9") (pinfunction "VBUS_2_B9") (pintype "passive"))
    )
    (net (code "58") (name "/VMAIN1") (class "Default")
      (node (ref "LB4") (pin "1") (pinfunction "1_1") (pintype "passive"))
      (node (ref "U6") (pin "55") (pinfunction "VBUS_55") (pintype "passive"))
      (node (ref "USB1") (pin "A4") (pinfunction "VBUS_A4") (pintype "passive"))
      (node (ref "USB1") (pin "A9") (pinfunction "VBUS_A9") (pintype "passive"))
      (node (ref "USB1") (pin "B4") (pinfunction "VBUS_B4") (pintype "passive"))
      (node (ref "USB1") (pin "B9") (pinfunction "VBUS_B9") (pintype "passive"))
    )
    (net (code "59") (name "/X1") (class "Default")
      (node (ref "C41") (pin "2") (pinfunction "2_2") (pintype "passive"))
      (node (ref "R8") (pin "1") (pinfunction "1_1") (pintype "passive"))
      (node (ref "U6") (pin "6") (pinfunction "X1_6") (pintype "passive"))
      (node (ref "Y1") (pin "1") (pinfunction "OSC1_1") (pintype "passive"))
    )
    (net (code "60") (name "/X2") (class "Default")
      (node (ref "C42") (pin "2") (pinfunction "2_2") (pintype "passive"))
      (node (ref "R8") (pin "2") (pinfunction "2_2") (pintype "passive"))
      (node (ref "U6") (pin "7") (pinfunction "X2_7") (pintype "passive"))
      (node (ref "Y1") (pin "3") (pinfunction "OSC2_3") (pintype "passive"))
    )
    (net (code "61") (name "GND") (class "Default")
      (node (ref "C11") (pin "1") (pinfunction "1_1") (pintype "passive"))
      (node (ref "C12") (pin "1") (pinfunction "1_1") (pintype "passive"))
      (node (ref "C13") (pin "1") (pinfunction "1_1") (pintype "passive"))
      (node (ref "C14") (pin "1") (pinfunction "1_1") (pintype "passive"))
      (node (ref "C15") (pin "1") (pinfunction "1_1") (pintype "passive"))
      (node (ref "C16") (pin "2") (pinfunction "2_2") (pintype "passive"))
      (node (ref "C17") (pin "1") (pinfunction "1_1") (pintype "passive"))
      (node (ref "C18") (pin "1") (pinfunction "1_1") (pintype "passive"))
      (node (ref "C19") (pin "2") (pinfunction "2_2") (pintype "passive"))
      (node (ref "C2") (pin "2") (pinfunction "2_2") (pintype "passive"))
      (node (ref "C20") (pin "2") (pinfunction "2_2") (pintype "passive"))
      (node (ref "C21") (pin "1") (pinfunction "1_1") (pintype "passive"))
      (node (ref "C22") (pin "1") (pinfunction "1_1") (pintype "passive"))
      (node (ref "C23") (pin "1") (pinfunction "1_1") (pintype "passive"))
      (node (ref "C24") (pin "1") (pinfunction "1_1") (pintype "passive"))
      (node (ref "C25") (pin "1") (pinfunction "1_1") (pintype "passive"))
      (node (ref "C26") (pin "1") (pinfunction "1_1") (pintype "passive"))
      (node (ref "C27") (pin "1") (pinfunction "1_1") (pintype "passive"))
      (node (ref "C28") (pin "1") (pinfunction "1_1") (pintype "passive"))
      (node (ref "C29") (pin "1") (pinfunction "1_1") (pintype "passive"))
      (node (ref "C3") (pin "2") (pinfunction "2_2") (pintype "passive"))
      (node (ref "C30") (pin "1") (pinfunction "1_1") (pintype "passive"))
      (node (ref "C31") (pin "1") (pinfunction "1_1") (pintype "passive"))
      (node (ref "C32") (pin "1") (pinfunction "1_1") (pintype "passive"))
      (node (ref "C33") (pin "1") (pinfunction "1_1") (pintype "passive"))
      (node (ref "C34") (pin "1") (pinfunction "1_1") (pintype "passive"))
      (node (ref "C35") (pin "1") (pinfunction "1_1") (pintype "passive"))
      (node (ref "C36") (pin "1") (pinfunction "1_1") (pintype "passive"))
      (node (ref "C37") (pin "1") (pinfunction "1_1") (pintype "passive"))
      (node (ref "C38") (pin "2") (pinfunction "2_2") (pintype "passive"))
      (node (ref "C39") (pin "1") (pinfunction "1_1") (pintype "passive"))
      (node (ref "C4") (pin "2") (pinfunction "2_2") (pintype "passive"))
      (node (ref "C40") (pin "1") (pinfunction "1_1") (pintype "passive"))
      (node (ref "C41") (pin "1") (pinfunction "1_1") (pintype "passive"))
      (node (ref "C42") (pin "1") (pinfunction "1_1") (pintype "passive"))
      (node (ref "C43") (pin "1") (pinfunction "1_1") (pintype "passive"))
      (node (ref "C44") (pin "2") (pinfunction "2_2") (pintype "passive"))
      (node (ref "C45") (pin "2") (pinfunction "2_2") (pintype "passive"))
      (node (ref "C47") (pin "1") (pinfunction "1_1") (pintype "passive"))
      (node (ref "C48") (pin "1") (pinfunction "1_1") (pintype "passive"))
      (node (ref "C49") (pin "2") (pinfunction "2_2") (pintype "passive"))
      (node (ref "C5") (pin "2") (pinfunction "2_2") (pintype "passive"))
      (node (ref "C50") (pin "1") (pinfunction "1_1") (pintype "passive"))
      (node (ref "C51") (pin "1") (pinfunction "1_1") (pintype "passive"))
      (node (ref "C52") (pin "2") (pinfunction "2_2") (pintype "passive"))
      (node (ref "C53") (pin "1") (pinfunction "1_1") (pintype "passive"))
      (node (ref "C6") (pin "1") (pinfunction "1_1") (pintype "passive"))
      (node (ref "C7") (pin "1") (pinfunction "1_1") (pintype "passive"))
      (node (ref "D10") (pin "1") (pinfunction "A_1") (pintype "passive"))
      (node (ref "D11") (pin "1") (pinfunction "A_1") (pintype "passive"))
      (node (ref "DOWN1") (pin "4") (pinfunction "GND_4") (pintype "power_in"))
      (node (ref "DOWN1") (pin "7") (pinfunction "GND_7") (pintype "power_in"))
      (node (ref "DOWN2") (pin "4") (pinfunction "GND_4") (pintype "power_in"))
      (node (ref "DOWN2") (pin "7") (pinfunction "GND_7") (pintype "power_in"))
      (node (ref "DOWN3") (pin "4") (pinfunction "GND_4") (pintype "power_in"))
      (node (ref "DOWN3") (pin "7") (pinfunction "GND_7") (pintype "power_in"))
      (node (ref "DOWN4") (pin "4") (pinfunction "GND_4") (pintype "power_in"))
      (node (ref "DOWN4") (pin "7") (pinfunction "GND_7") (pintype "power_in"))
      (node (ref "R1") (pin "2") (pinfunction "2_2") (pintype "passive"))
      (node (ref "R10") (pin "1") (pinfunction "1_1") (pintype "passive"))
      (node (ref "R12") (pin "2") (pinfunction "2_2") (pintype "passive"))
      (node (ref "R13") (pin "2") (pinfunction "2_2") (pintype "passive"))
      (node (ref "R14") (pin "2") (pinfunction "2_2") (pintype "passive"))
      (node (ref "R15") (pin "1") (pinfunction "1_1") (pintype "passive"))
      (node (ref "R16") (pin "1") (pinfunction "1_1") (pintype "passive"))
      (node (ref "R17") (pin "1") (pinfunction "1_1") (pintype "passive"))
      (node (ref "R18") (pin "1") (pinfunction "1_1") (pintype "passive"))
      (node (ref "R19") (pin "2") (pinfunction "2_2") (pintype "passive"))
      (node (ref "R3") (pin "2") (pinfunction "2_2") (pintype "passive"))
      (node (ref "R30") (pin "2") (pinfunction "2_2") (pintype "passive"))
      (node (ref "R31") (pin "2") (pinfunction "2_2") (pintype "passive"))
      (node (ref "R32") (pin "2") (pinfunction "2_2") (pintype "passive"))
      (node (ref "R33") (pin "2") (pinfunction "2_2") (pintype "passive"))
      (node (ref "R34") (pin "2") (pinfunction "2_2") (pintype "passive"))
      (node (ref "R35") (pin "2") (pinfunction "2_2") (pintype "passive"))
      (node (ref "R36") (pin "2") (pinfunction "2_2") (pintype "passive"))
      (node (ref "R4") (pin "2") (pinfunction "2_2") (pintype "passive"))
      (node (ref "R5") (pin "2") (pinfunction "2_2") (pintype "passive"))
      (node (ref "R6") (pin "2") (pinfunction "2_2") (pintype "passive"))
      (node (ref "R9") (pin "2") (pinfunction "2_2") (pintype "passive"))
      (node (ref "U1") (pin "11") (pinfunction "PAD_11") (pintype "passive"))
      (node (ref "U1") (pin "9") (pinfunction "GND_9") (pintype "passive"))
      (node (ref "U10") (pin "6") (pinfunction "GND_6") (pintype "passive"))
      (node (ref "U2") (pin "9") (pinfunction "GND_9") (pintype "passive"))
      (node (ref "U3") (pin "9") (pinfunction "GND_9") (pintype "passive"))
      (node (ref "U4") (pin "2") (pinfunction "GND_2") (pintype "passive"))
      (node (ref "U5") (pin "9") (pinfunction "GND_9") (pintype "passive"))
      (node (ref "U6") (pin "11") (pinfunction "GND_11") (pintype "passive"))
      (node (ref "U6") (pin "18") (pinfunction "GND_18") (pintype "passive"))
      (node (ref "U6") (pin "26") (pinfunction "GND_26") (pintype "passive"))
      (node (ref "U6") (pin "33") (pinfunction "GND_33") (pintype "passive"))
      (node (ref "U6") (pin "40") (pinfunction "GND_40") (pintype "passive"))
      (node (ref "U6") (pin "67") (pinfunction "GND_67") (pintype "passive"))
      (node (ref "U6") (pin "G1") (pinfunction "G1_G1") (pintype "passive"))
      (node (ref "U7") (pin "9") (pinfunction "GND_9") (pintype "passive"))
      (node (ref "U8") (pin "4") (pinfunction "VSS_4") (pintype "passive"))
      (node (ref "U9") (pin "6") (pinfunction "GND_6") (pintype "passive"))
      (node (ref "USB1") (pin "A1") (pinfunction "GND_A1") (pintype "passive"))
      (node (ref "USB1") (pin "A12") (pinfunction "GND_A12") (pintype "passive"))
      (node (ref "USB1") (pin "B1") (pinfunction "GND_B1") (pintype "passive"))
      (node (ref "USB1") (pin "B12") (pinfunction "GND_B12") (pintype "passive"))
      (node (ref "USB2") (pin "A12") (pinfunction "GND_1_A12") (pintype "passive"))
      (node (ref "USB2") (pin "B12") (pinfunction "GND_2_B12") (pintype "passive"))
    )
    (net (code "62") (name "Net-(D2-PadK)") (class "Default")
      (node (ref "D2") (pin "K") (pinfunction "K_K") (pintype "passive"))
      (node (ref "D4") (pin "K") (pinfunction "K_K") (pintype "passive"))
      (node (ref "R15") (pin "2") (pinfunction "2_2") (pintype "passive"))
    )
    (net (code "63") (name "Net-(D3-PadK)") (class "Default")
      (node (ref "D3") (pin "K") (pinfunction "K_K") (pintype "passive"))
      (node (ref "D5") (pin "K") (pinfunction "K_K") (pintype "passive"))
      (node (ref "R16") (pin "2") (pinfunction "2_2") (pintype "passive"))
    )
    (net (code "64") (name "Net-(D6-PadK)") (class "Default")
      (node (ref "D6") (pin "K") (pinfunction "K_K") (pintype "passive"))
      (node (ref "D8") (pin "K") (pinfunction "K_K") (pintype "passive"))
      (node (ref "R17") (pin "2") (pinfunction "2_2") (pintype "passive"))
    )
    (net (code "65") (name "Net-(D7-PadK)") (class "Default")
      (node (ref "D7") (pin "K") (pinfunction "K_K") (pintype "passive"))
      (node (ref "D9") (pin "K") (pinfunction "K_K") (pintype "passive"))
      (node (ref "R18") (pin "2") (pinfunction "2_2") (pintype "passive"))
    )
    (net (code "66") (name "Net-(DOWN1-VCC)") (class "Default")
      (node (ref "DOWN1") (pin "1") (pinfunction "VCC_1") (pintype "power_in"))
      (node (ref "LB1") (pin "2") (pinfunction "2_2") (pintype "passive"))
    )
    (net (code "67") (name "Net-(DOWN2-VCC)") (class "Default")
      (node (ref "DOWN2") (pin "1") (pinfunction "VCC_1") (pintype "power_in"))
      (node (ref "LB5") (pin "2") (pinfunction "2_2") (pintype "passive"))
    )
    (net (code "68") (name "Net-(DOWN3-VCC)") (class "Default")
      (node (ref "DOWN3") (pin "1") (pinfunction "VCC_1") (pintype "power_in"))
      (node (ref "LB8") (pin "2") (pinfunction "2_2") (pintype "passive"))
    )
    (net (code "69") (name "Net-(DOWN4-VCC)") (class "Default")
      (node (ref "DOWN4") (pin "1") (pinfunction "VCC_1") (pintype "power_in"))
      (node (ref "LB9") (pin "2") (pinfunction "2_2") (pintype "passive"))
    )
    (net (code "70") (name "Net-(U4-FB)") (class "Default")
      (node (ref "C46") (pin "1") (pinfunction "1_1") (pintype "passive"))
      (node (ref "R11") (pin "2") (pinfunction "2_2") (pintype "passive"))
      (node (ref "R13") (pin "1") (pinfunction "1_1") (pintype "passive"))
      (node (ref "U4") (pin "5") (pinfunction "FB_5") (pintype "passive"))
    )
    (net (code "71") (name "Net-(U4-LX)") (class "Default")
      (node (ref "LB7") (pin "1") (pinfunction "1_1") (pintype "passive"))
      (node (ref "U4") (pin "3") (pinfunction "LX_3") (pintype "passive"))
    )
    (net (code "72") (name "Net-(U8-~{HOLD})") (class "Default")
      (node (ref "R21") (pin "1") (pinfunction "1_1") (pintype "passive"))
      (node (ref "U8") (pin "7") (pinfunction "~{HOLD}_7") (pintype "passive"))
    )
    (net (code "73") (name "Net-(U8-~{WP})") (class "Default")
      (node (ref "R20") (pin "2") (pinfunction "2_2") (pintype "passive"))
      (node (ref "R30") (pin "1") (pinfunction "1_1") (pintype "passive"))
      (node (ref "U8") (pin "3") (pinfunction "~{WP}_3") (pintype "passive"))
    )
    (net (code "74") (name "Net-(USB1-TX1+)") (class "Default")
      (node (ref "C1") (pin "1") (pinfunction "1_1") (pintype "passive"))
      (node (ref "USB1") (pin "A2") (pinfunction "TX1+_A2") (pintype "passive"))
    )
    (net (code "75") (name "Net-(USB1-TX1-)") (class "Default")
      (node (ref "C8") (pin "1") (pinfunction "1_1") (pintype "passive"))
      (node (ref "USB1") (pin "A3") (pinfunction "TX1-_A3") (pintype "passive"))
    )
    (net (code "76") (name "Net-(USB1-TX2+)") (class "Default")
      (node (ref "C10") (pin "2") (pinfunction "2_2") (pintype "passive"))
      (node (ref "USB1") (pin "B2") (pinfunction "TX2+_B2") (pintype "passive"))
    )
    (net (code "77") (name "Net-(USB1-TX2-)") (class "Default")
      (node (ref "C9") (pin "2") (pinfunction "2_2") (pintype "passive"))
      (node (ref "USB1") (pin "B3") (pinfunction "TX2-_B3") (pintype "passive"))
    )
    (net (code "78") (name "SHIEL3") (class "Default")
      (node (ref "C11") (pin "2") (pinfunction "2_2") (pintype "passive"))
      (node (ref "R4") (pin "1") (pinfunction "1_1") (pintype "passive"))
    )
    (net (code "79") (name "SHIELD1") (class "Default")
      (node (ref "C18") (pin "2") (pinfunction "2_2") (pintype "passive"))
      (node (ref "R6") (pin "1") (pinfunction "1_1") (pintype "passive"))
      (node (ref "USB1") (pin "1") (pinfunction "SH1_1") (pintype "passive"))
      (node (ref "USB1") (pin "2") (pinfunction "SH2_2") (pintype "passive"))
      (node (ref "USB1") (pin "3") (pinfunction "SH3_3") (pintype "passive"))
      (node (ref "USB1") (pin "4") (pinfunction "SH4_4") (pintype "passive"))
    )
    (net (code "80") (name "SHIELD2") (class "Default")
      (node (ref "C43") (pin "2") (pinfunction "2_2") (pintype "passive"))
      (node (ref "R12") (pin "1") (pinfunction "1_1") (pintype "passive"))
      (node (ref "USB2") (pin "MH1") (pinfunction "MH1_MH1") (pintype "passive"))
      (node (ref "USB2") (pin "MH2") (pinfunction "MH2_MH2") (pintype "passive"))
      (node (ref "USB2") (pin "MH3") (pinfunction "MH3_MH3") (pintype "passive"))
      (node (ref "USB2") (pin "MH4") (pinfunction "MH4_MH4") (pintype "passive"))
    )
    (net (code "81") (name "SHIELD3") (class "Default")
      (node (ref "DOWN1") (pin "G1") (pinfunction "HAND1_G1") (pintype "passive"))
      (node (ref "DOWN1") (pin "G2") (pinfunction "HAND2_G2") (pintype "passive"))
    )
    (net (code "82") (name "SHIELD4") (class "Default")
      (node (ref "C28") (pin "2") (pinfunction "2_2") (pintype "passive"))
      (node (ref "DOWN2") (pin "G1") (pinfunction "HAND1_G1") (pintype "passive"))
      (node (ref "DOWN2") (pin "G2") (pinfunction "HAND2_G2") (pintype "passive"))
      (node (ref "R9") (pin "1") (pinfunction "1_1") (pintype "passive"))
    )
    (net (code "83") (name "SHIELD5") (class "Default")
      (node (ref "C48") (pin "2") (pinfunction "2_2") (pintype "passive"))
      (node (ref "DOWN3") (pin "G1") (pinfunction "HAND1_G1") (pintype "passive"))
      (node (ref "DOWN3") (pin "G2") (pinfunction "HAND2_G2") (pintype "passive"))
      (node (ref "R14") (pin "1") (pinfunction "1_1") (pintype "passive"))
    )
    (net (code "84") (name "SHIELD6") (class "Default")
      (node (ref "C51") (pin "2") (pinfunction "2_2") (pintype "passive"))
      (node (ref "DOWN4") (pin "G1") (pinfunction "HAND1_G1") (pintype "passive"))
      (node (ref "DOWN4") (pin "G2") (pinfunction "HAND2_G2") (pintype "passive"))
      (node (ref "R19") (pin "1") (pinfunction "1_1") (pintype "passive"))
    )
    (net (code "85") (name "VAUX") (class "Default")
      (node (ref "C2") (pin "1") (pinfunction "1_1") (pintype "passive"))
      (node (ref "C6") (pin "2") (pinfunction "2_2") (pintype "passive"))
      (node (ref "D1") (pin "1") (pinfunction "A_1") (pintype "passive"))
      (node (ref "D10") (pin "2") (pinfunction "K_2") (pintype "passive"))
      (node (ref "LB6") (pin "2") (pinfunction "2_2") (pintype "passive"))
      (node (ref "R1") (pin "1") (pinfunction "1_1") (pintype "passive"))
      (node (ref "R2") (pin "2") (pinfunction "2_2") (pintype "passive"))
    )
    (net (code "86") (name "VCC") (class "Default")
      (node (ref "C19") (pin "1") (pinfunction "1_1") (pintype "passive"))
      (node (ref "C24") (pin "2") (pinfunction "2_2") (pintype "passive"))
      (node (ref "C44") (pin "1") (pinfunction "1_1") (pintype "passive"))
      (node (ref "D1") (pin "2") (pinfunction "K_2") (pintype "passive"))
      (node (ref "Q1") (pin "2") (pinfunction "SOURCE_2") (pintype "passive"))
      (node (ref "R7") (pin "2") (pinfunction "2_2") (pintype "passive"))
      (node (ref "U1") (pin "2") (pinfunction "VCC_2") (pintype "passive"))
      (node (ref "U10") (pin "7") (pinfunction "IN_7") (pintype "passive"))
      (node (ref "U4") (pin "1") (pinfunction "EN_1") (pintype "passive"))
      (node (ref "U4") (pin "4") (pinfunction "VIN_4") (pintype "passive"))
      (node (ref "U6") (pin "86") (pinfunction "V5_LDO_86") (pintype "passive"))
      (node (ref "U9") (pin "7") (pinfunction "IN_7") (pintype "passive"))
    )
    (net (code "87") (name "VD12") (class "Default")
      (node (ref "C12") (pin "2") (pinfunction "2_2") (pintype "passive"))
      (node (ref "C13") (pin "2") (pinfunction "2_2") (pintype "passive"))
      (node (ref "C14") (pin "2") (pinfunction "2_2") (pintype "passive"))
      (node (ref "C15") (pin "2") (pinfunction "2_2") (pintype "passive"))
      (node (ref "C45") (pin "1") (pinfunction "1_1") (pintype "passive"))
      (node (ref "C46") (pin "2") (pinfunction "2_2") (pintype "passive"))
      (node (ref "C47") (pin "2") (pinfunction "2_2") (pintype "passive"))
      (node (ref "LB2") (pin "1") (pinfunction "1_1") (pintype "passive"))
      (node (ref "LB7") (pin "2") (pinfunction "2_2") (pintype "passive"))
      (node (ref "R11") (pin "1") (pinfunction "1_1") (pintype "passive"))
      (node (ref "U6") (pin "44") (pinfunction "DVDD12_44") (pintype "passive"))
      (node (ref "U6") (pin "49") (pinfunction "DVDD12_49") (pintype "passive"))
      (node (ref "U6") (pin "57") (pinfunction "DVDD12_57") (pintype "passive"))
      (node (ref "U6") (pin "75") (pinfunction "DVDD12_75") (pintype "passive"))
    )
    (net (code "88") (name "VD33") (class "Default")
      (node (ref "C20") (pin "1") (pinfunction "1_1") (pintype "passive"))
      (node (ref "C25") (pin "2") (pinfunction "2_2") (pintype "passive"))
      (node (ref "C26") (pin "2") (pinfunction "2_2") (pintype "passive"))
      (node (ref "C27") (pin "2") (pinfunction "2_2") (pintype "passive"))
      (node (ref "C4") (pin "1") (pinfunction "1_1") (pintype "passive"))
      (node (ref "LB3") (pin "1") (pinfunction "1_1") (pintype "passive"))
      (node (ref "R20") (pin "1") (pinfunction "1_1") (pintype "passive"))
      (node (ref "R21") (pin "2") (pinfunction "2_2") (pintype "passive"))
      (node (ref "R22") (pin "1") (pinfunction "1_1") (pintype "passive"))
      (node (ref "R23") (pin "1") (pinfunction "1_1") (pintype "passive"))
      (node (ref "R24") (pin "1") (pinfunction "1_1") (pintype "passive"))
      (node (ref "R25") (pin "1") (pinfunction "1_1") (pintype "passive"))
      (node (ref "R26") (pin "1") (pinfunction "1_1") (pintype "passive"))
      (node (ref "R27") (pin "1") (pinfunction "1_1") (pintype "passive"))
      (node (ref "R28") (pin "1") (pinfunction "1_1") (pintype "passive"))
      (node (ref "R29") (pin "1") (pinfunction "1_1") (pintype "passive"))
      (node (ref "U6") (pin "58") (pinfunction "DVDD_58") (pintype "passive"))
      (node (ref "U6") (pin "73") (pinfunction "DVDD_73") (pintype "passive"))
      (node (ref "U6") (pin "85") (pinfunction "V33_OUT_85") (pintype "passive"))
      (node (ref "U8") (pin "8") (pinfunction "VCC_8") (pintype "passive"))
    )
    (net (code "89") (name "VDP1") (class "Default")
      (node (ref "C16") (pin "1") (pinfunction "1_1") (pintype "passive"))
      (node (ref "C17") (pin "2") (pinfunction "2_2") (pintype "passive"))
      (node (ref "LB1") (pin "1") (pinfunction "1_1") (pintype "passive"))
      (node (ref "U2") (pin "2") (pinfunction "VCC_2") (pintype "passive"))
      (node (ref "U9") (pin "8") (pinfunction "OUTA_8") (pintype "passive"))
    )
    (net (code "90") (name "VDP2") (class "Default")
      (node (ref "C38") (pin "1") (pinfunction "1_1") (pintype "passive"))
      (node (ref "C39") (pin "2") (pinfunction "2_2") (pintype "passive"))
      (node (ref "LB5") (pin "1") (pinfunction "1_1") (pintype "passive"))
      (node (ref "U3") (pin "2") (pinfunction "VCC_2") (pintype "passive"))
      (node (ref "U9") (pin "5") (pinfunction "OUTB_5") (pintype "passive"))
    )
    (net (code "91") (name "VDP3") (class "Default")
      (node (ref "C49") (pin "1") (pinfunction "1_1") (pintype "passive"))
      (node (ref "C50") (pin "2") (pinfunction "2_2") (pintype "passive"))
      (node (ref "LB8") (pin "1") (pinfunction "1_1") (pintype "passive"))
      (node (ref "U10") (pin "5") (pinfunction "OUTB_5") (pintype "passive"))
      (node (ref "U10") (pin "8") (pinfunction "OUTA_8") (pintype "passive"))
      (node (ref "U5") (pin "2") (pinfunction "VCC_2") (pintype "passive"))
    )
    (net (code "92") (name "VDP4") (class "Default")
      (node (ref "C52") (pin "1") (pinfunction "1_1") (pintype "passive"))
      (node (ref "C53") (pin "2") (pinfunction "2_2") (pintype "passive"))
      (node (ref "LB9") (pin "1") (pinfunction "1_1") (pintype "passive"))
      (node (ref "U7") (pin "2") (pinfunction "VCC_2") (pintype "passive"))
    )
    (net (code "93") (name "VMAIN") (class "Default")
      (node (ref "C3") (pin "1") (pinfunction "1_1") (pintype "passive"))
      (node (ref "C7") (pin "2") (pinfunction "2_2") (pintype "passive"))
      (node (ref "D11") (pin "2") (pinfunction "K_2") (pintype "passive"))
      (node (ref "LB4") (pin "2") (pinfunction "2_2") (pintype "passive"))
      (node (ref "Q1") (pin "3") (pinfunction "DRAIN_3") (pintype "passive"))
    )
    (net (code "94") (name "VP12") (class "Default")
      (node (ref "C29") (pin "2") (pinfunction "2_2") (pintype "passive"))
      (node (ref "C30") (pin "2") (pinfunction "2_2") (pintype "passive"))
      (node (ref "C31") (pin "2") (pinfunction "2_2") (pintype "passive"))
      (node (ref "C32") (pin "2") (pinfunction "2_2") (pintype "passive"))
      (node (ref "C33") (pin "2") (pinfunction "2_2") (pintype "passive"))
      (node (ref "C34") (pin "2") (pinfunction "2_2") (pintype "passive"))
      (node (ref "C35") (pin "2") (pinfunction "2_2") (pintype "passive"))
      (node (ref "C36") (pin "2") (pinfunction "2_2") (pintype "passive"))
      (node (ref "C37") (pin "2") (pinfunction "2_2") (pintype "passive"))
      (node (ref "LB2") (pin "2") (pinfunction "2_2") (pintype "passive"))
      (node (ref "U6") (pin "14") (pinfunction "VP12_14") (pintype "passive"))
      (node (ref "U6") (pin "15") (pinfunction "VP12_15") (pintype "passive"))
      (node (ref "U6") (pin "21") (pinfunction "VP12_21") (pintype "passive"))
      (node (ref "U6") (pin "23") (pinfunction "VP12_23") (pintype "passive"))
      (node (ref "U6") (pin "29") (pinfunction "VP12_29") (pintype "passive"))
      (node (ref "U6") (pin "30") (pinfunction "VP12_30") (pintype "passive"))
      (node (ref "U6") (pin "36") (pinfunction "VP12_36") (pintype "passive"))
      (node (ref "U6") (pin "37") (pinfunction "VP12_37") (pintype "passive"))
      (node (ref "U6") (pin "43") (pinfunction "VP12_43") (pintype "passive"))
    )
    (net (code "95") (name "VP33") (class "Default")
      (node (ref "C21") (pin "2") (pinfunction "2_2") (pintype "passive"))
      (node (ref "C22") (pin "2") (pinfunction "2_2") (pintype "passive"))
      (node (ref "C23") (pin "2") (pinfunction "2_2") (pintype "passive"))
      (node (ref "C5") (pin "1") (pinfunction "1_1") (pintype "passive"))
      (node (ref "LB3") (pin "2") (pinfunction "2_2") (pintype "passive"))
      (node (ref "U6") (pin "63") (pinfunction "AVDD_63") (pintype "passive"))
      (node (ref "U6") (pin "66") (pinfunction "AVDD_66") (pintype "passive"))
      (node (ref "U6") (pin "70") (pinfunction "AVDD_70") (pintype "passive"))
    )
    (net (code "96") (name "unconnected-(R2-Pad1)") (class "Default")
      (node (ref "R2") (pin "1") (pinfunction "1_1") (pintype "passive"))
    )
    (net (code "97") (name "unconnected-(U1-NC-Pad3)") (class "Default")
      (node (ref "U1") (pin "3") (pinfunction "NC_3") (pintype "passive+no_connect"))
    )
    (net (code "98") (name "unconnected-(U1-NC-Pad8)") (class "Default")
      (node (ref "U1") (pin "8") (pinfunction "NC_8") (pintype "passive+no_connect"))
    )
    (net (code "99") (name "unconnected-(U2-NC-Pad3)") (class "Default")
      (node (ref "U2") (pin "3") (pinfunction "NC_3") (pintype "passive+no_connect"))
    )
    (net (code "100") (name "unconnected-(U2-NC-Pad8)") (class "Default")
      (node (ref "U2") (pin "8") (pinfunction "NC_8") (pintype "passive+no_connect"))
    )
    (net (code "101") (name "unconnected-(U2-PAD-Pad11)") (class "Default")
      (node (ref "U2") (pin "11") (pinfunction "PAD_11") (pintype "passive"))
    )
    (net (code "102") (name "unconnected-(U3-NC-Pad3)") (class "Default")
      (node (ref "U3") (pin "3") (pinfunction "NC_3") (pintype "passive+no_connect"))
    )
    (net (code "103") (name "unconnected-(U3-NC-Pad8)") (class "Default")
      (node (ref "U3") (pin "8") (pinfunction "NC_8") (pintype "passive+no_connect"))
    )
    (net (code "104") (name "unconnected-(U3-PAD-Pad11)") (class "Default")
      (node (ref "U3") (pin "11") (pinfunction "PAD_11") (pintype "passive"))
    )
    (net (code "105") (name "unconnected-(U5-NC-Pad3)") (class "Default")
      (node (ref "U5") (pin "3") (pinfunction "NC_3") (pintype "passive+no_connect"))
    )
    (net (code "106") (name "unconnected-(U5-NC-Pad8)") (class "Default")
      (node (ref "U5") (pin "8") (pinfunction "NC_8") (pintype "passive+no_connect"))
    )
    (net (code "107") (name "unconnected-(U5-PAD-Pad11)") (class "Default")
      (node (ref "U5") (pin "11") (pinfunction "PAD_11") (pintype "passive"))
    )
    (net (code "108") (name "unconnected-(U6-NC-Pad4)") (class "Default")
      (node (ref "U6") (pin "4") (pinfunction "NC_4") (pintype "passive"))
    )
    (net (code "109") (name "unconnected-(U6-NC-Pad5)") (class "Default")
      (node (ref "U6") (pin "5") (pinfunction "NC_5") (pintype "passive"))
    )
    (net (code "110") (name "unconnected-(U6-NC-Pad8)") (class "Default")
      (node (ref "U6") (pin "8") (pinfunction "NC_8") (pintype "passive"))
    )
    (net (code "111") (name "unconnected-(U6-NC-Pad22)") (class "Default")
      (node (ref "U6") (pin "22") (pinfunction "NC_22") (pintype "passive"))
    )
    (net (code "112") (name "unconnected-(U6-TEST-Pad76)") (class "Default")
      (node (ref "U6") (pin "76") (pinfunction "TEST_76") (pintype "passive+no_connect"))
    )
    (net (code "113") (name "unconnected-(U7-NC-Pad3)") (class "Default")
      (node (ref "U7") (pin "3") (pinfunction "NC_3") (pintype "passive+no_connect"))
    )
    (net (code "114") (name "unconnected-(U7-NC-Pad8)") (class "Default")
      (node (ref "U7") (pin "8") (pinfunction "NC_8") (pintype "passive+no_connect"))
    )
    (net (code "115") (name "unconnected-(U7-PAD-Pad11)") (class "Default")
      (node (ref "U7") (pin "11") (pinfunction "PAD_11") (pintype "passive"))
    )
    (net (code "116") (name "unconnected-(USB1-SBU1-PadA8)") (class "Default")
      (node (ref "USB1") (pin "A8") (pinfunction "SBU1_A8") (pintype "passive+no_connect"))
    )
    (net (code "117") (name "unconnected-(USB1-SBU2-PadB8)") (class "Default")
      (node (ref "USB1") (pin "B8") (pinfunction "SBU2_B8") (pintype "passive+no_connect"))
    )
    (net (code "118") (name "unconnected-(USB2-CC1-PadA5)") (class "Default")
      (node (ref "USB2") (pin "A5") (pinfunction "CC1_A5") (pintype "passive+no_connect"))
    )
    (net (code "119") (name "unconnected-(USB2-CC2-PadB5)") (class "Default")
      (node (ref "USB2") (pin "B5") (pinfunction "CC2_B5") (pintype "passive+no_connect"))
    )
  )
)
